# CLK_DS1391U_RTC.net
KiCad netlist of a schematic drawn in Altium Designer
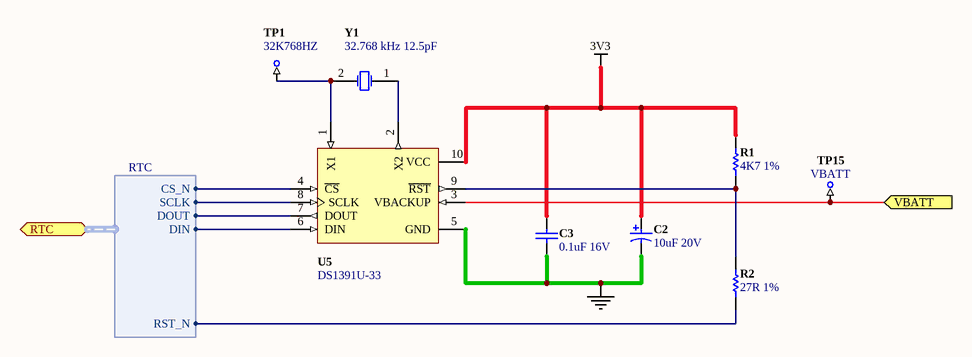
[diagram p0: CLK_DS1391U_RTC.SchDoc]

(export (version "E")
  (design (tool "Eeschema 10.0.6"))
  (components
    (comp (ref "C2")
      (value "10uF 20V")
      (footprint "CAPC3528-STAR")
      (description "Capacitor, Tantalum, 10uF 10% 20V MCCT-B (3528)")
      (fields (field (name "TOLERANCE") "10 %"))
      (libsource (lib "altium-import") (part "root_0_CAP-P_"))
    )
    (comp (ref "C3")
      (value "0.1uF 16V")
      (footprint "CAPC1005-STAR")
      (description "Capacitor, Ceramic, 0.1uF 10% 16V 0402 (1005) X7R")
      (fields (field (name "TOLERANCE") "10 %"))
      (libsource (lib "altium-import") (part "root_0_mirrored_CAP-NP_"))
    )
    (comp (ref "R1")
      (value "4K7 1%")
      (footprint "RESC1005-STAR")
      (description "Resistor, 4K7 1% 0402 (1005)")
      (fields (field (name "TOLERANCE") "1 %"))
      (libsource (lib "altium-import") (part "root_2_RES_"))
    )
    (comp (ref "R2")
      (value "27R 1%")
      (footprint "RESC1005-STAR")
      (description "Resistor, 27R 1% 0402 (1005)")
      (fields (field (name "TOLERANCE") "1 %"))
      (libsource (lib "AltiumDesignLibrary") (part "RES"))
    )
    (comp (ref "TP1")
      (value "32K768HZ")
      (footprint "TestPin")
      (description "Test Point, PCB Mount with Silkscreen Box")
      (libsource (lib "AltiumDesignLibrary") (part "TestPin"))
    )
    (comp (ref "TP15")
      (value "VBATT")
      (footprint "TestPin")
      (description "Test Point, PCB Mount with Silkscreen Box")
      (libsource (lib "AltiumDesignLibrary") (part "TestPin"))
    )
    (comp (ref "U5")
      (value "DS1391U-33")
      (footprint "SSOP50P490-10")
      (description "DS1391U-33, SPI Real-Time Clock with Trickle Charger, 3.3V, 10-Pin uMax/uSOP")
      (libsource (lib "altium-import") (part "root_0_DS1391_"))
    )
    (comp (ref "Y1")
      (value "32.768 kHz 12.5pF")
      (footprint "XTAL QSC26 QSMC-200S Combi")
      (description "Crystal, 32.768 KHz Surface Mount")
      (libsource (lib "altium-import") (part "root_0_CRYS_"))
    )
  )
  (nets
    (net (code "2") (name "/CS_N") (class "Default")
      (node (ref "U5") (pin "4") (pinfunction "~{CS}_4") (pintype "input"))
    )
    (net (code "3") (name "/DIN") (class "Default")
      (node (ref "U5") (pin "6") (pinfunction "DIN_6") (pintype "input"))
    )
    (net (code "4") (name "/DOUT") (class "Default")
      (node (ref "U5") (pin "7") (pinfunction "DOUT_7") (pintype "output"))
    )
    (net (code "5") (name "/RST_N") (class "Default")
      (node (ref "R2") (pin "1") (pinfunction "1_1") (pintype "passive"))
    )
    (net (code "6") (name "/SCLK") (class "Default")
      (node (ref "U5") (pin "8") (pinfunction "SCLK_8") (pintype "input"))
    )
    (net (code "7") (name "/VBATT") (class "Default")
      (node (ref "TP15") (pin "1") (pinfunction "1_1") (pintype "input"))
      (node (ref "U5") (pin "3") (pinfunction "VBACKUP_3") (pintype "input"))
    )
    (net (code "9") (name "3V3") (class "Default")
      (node (ref "C2") (pin "1") (pinfunction "1_1") (pintype "passive"))
      (node (ref "C3") (pin "1") (pinfunction "1_1") (pintype "passive"))
      (node (ref "R1") (pin "2") (pinfunction "2_2") (pintype "passive"))
      (node (ref "U5") (pin "10") (pinfunction "VCC_10") (pintype "power_in"))
    )
    (net (code "10") (name "GND") (class "Default")
      (node (ref "C2") (pin "2") (pinfunction "2_2") (pintype "passive"))
      (node (ref "C3") (pin "2") (pinfunction "2_2") (pintype "passive"))
      (node (ref "U5") (pin "5") (pinfunction "GND_5") (pintype "power_in"))
    )
    (net (code "11") (name "Net-(U5-X1)") (class "Default")
      (node (ref "TP1") (pin "1") (pinfunction "1_1") (pintype "input"))
      (node (ref "U5") (pin "1") (pinfunction "X1_1") (pintype "input"))
      (node (ref "Y1") (pin "2") (pinfunction "OSC2_2") (pintype "passive"))
    )
    (net (code "12") (name "Net-(U5-X2)") (class "Default")
      (node (ref "U5") (pin "2") (pinfunction "X2_2") (pintype "output"))
      (node (ref "Y1") (pin "1") (pinfunction "OSC1_1") (pintype "passive"))
    )
    (net (code "13") (name "Net-(U5-~{RST})") (class "Default")
      (node (ref "R1") (pin "1") (pinfunction "1_1") (pintype "passive"))
      (node (ref "R2") (pin "2") (pinfunction "2_2") (pintype "passive"))
      (node (ref "U5") (pin "9") (pinfunction "~{RST}_9") (pintype "output"))
    )
  )
)
